# select_load.net
KiCad netlist of a schematic drawn in Altium Designer
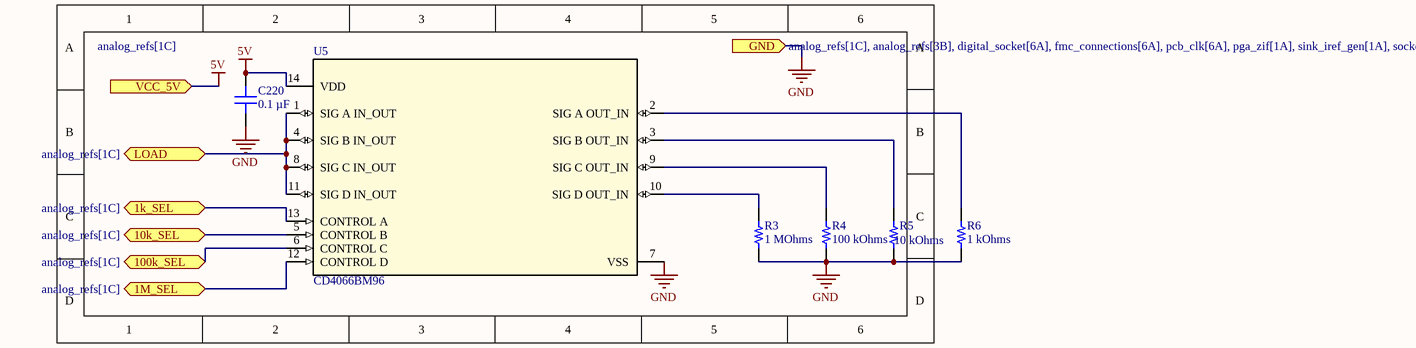
[diagram p0: select_load.SchDoc]

(export (version "E")
  (design (tool "Eeschema 10.0.6"))
  (components
    (comp (ref "C220")
      (value "0.1 µF")
      (footprint "CAP 0805_2012")
      (description "CAP CER 0.1UF 16V X7R 0805")
      (fields
        (field (name "PART NUMBER") "160R15W104KV4T")
        (field (name "CAPACITANCE") "0.1 µF")
        (field (name "MANUFACTURER") "Johanson Dielectrics Inc.")
      )
      (libsource (lib "Celestial Altium Library - altium_library") (part "Capacitor"))
    )
    (comp (ref "R3")
      (value "1 MOhms")
      (footprint "YAGEO RES 0805_2012")
      (description "RES 1 MOHM 1% 1/4W 0805")
      (fields (field (name "PART NUMBER") "AC0805FR-7W1ML") (field (name "MANUFACTURER") "Yageo"))
      (libsource (lib "Celestial Altium Library - altium_library") (part "Resistor"))
    )
    (comp (ref "R4")
      (value "100 kOhms")
      (footprint "RES 0805_2012")
      (description "3430 A2 1% 100K 100PPM 1K RL")
      (fields
        (field (name "PART NUMBER") "3430A2F100KTDF")
        (field (name "MANUFACTURER") "TE Connectivity Passive Product")
      )
      (libsource (lib "Celestial Altium Library - altium_library") (part "Resistor"))
    )
    (comp (ref "R5")
      (value "10 kOhms")
      (footprint "RES 0805_2012")
      (description "3430 A2 1% 10K 100PPM 1K RL")
      (fields
        (field (name "PART NUMBER") "3430A2F10KTDF")
        (field (name "MANUFACTURER") "TE Connectivity Passive Product")
      )
      (libsource (lib "Celestial Altium Library - altium_library") (part "Resistor"))
    )
    (comp (ref "R6")
      (value "1 kOhms")
      (footprint "RES 0805_2012")
      (description "RESHIGHPOWERA 0805 1K 1% 1/2W TC")
      (fields (field (name "PART NUMBER") "CHP0805AFX-1001ELF") (field (name "MANUFACTURER") "Bourns Inc."))
      (libsource (lib "Celestial Altium Library - altium_library") (part "Resistor"))
    )
    (comp (ref "U5")
      (value "CD4066BM96")
      (footprint "D0014A_N")
      (description "10-pA on-state leakage current, 20-V, 1:1 (SPST), 4-channel analog switch 14-SOIC -55 to 125")
      (fields (field (name "COPYRIGHT") "Copyright (C) 2026 Ultra Librarian. All rights reserved."))
      (libsource (lib "Logic") (part "CD4066BM96"))
    )
  )
  (nets
    (net (code "1") (name "/1M_SEL") (class "Default")
      (node (ref "U5") (pin "12") (pinfunction "CONTROL_D_12") (pintype "input"))
    )
    (net (code "2") (name "/1k_SEL") (class "Default")
      (node (ref "U5") (pin "13") (pinfunction "CONTROL_A_13") (pintype "input"))
    )
    (net (code "3") (name "/10k_SEL") (class "Default")
      (node (ref "U5") (pin "5") (pinfunction "CONTROL_B_5") (pintype "input"))
    )
    (net (code "4") (name "/100k_SEL") (class "Default")
      (node (ref "U5") (pin "6") (pinfunction "CONTROL_C_6") (pintype "input"))
    )
    (net (code "5") (name "/LOAD") (class "Default")
      (node (ref "U5") (pin "1") (pinfunction "SIG_A_IN_OUT_1") (pintype "bidirectional"))
      (node (ref "U5") (pin "11") (pinfunction "SIG_D_IN_OUT_11") (pintype "bidirectional"))
      (node (ref "U5") (pin "4") (pinfunction "SIG_B_IN_OUT_4") (pintype "bidirectional"))
      (node (ref "U5") (pin "8") (pinfunction "SIG_C_IN_OUT_8") (pintype "bidirectional"))
    )
    (net (code "6") (name "5V") (class "Default")
      (node (ref "C220") (pin "2") (pinfunction "2_2") (pintype "passive"))
      (node (ref "U5") (pin "14") (pinfunction "VDD_14") (pintype "power_in"))
    )
    (net (code "7") (name "GND") (class "Default")
      (node (ref "C220") (pin "1") (pinfunction "1_1") (pintype "passive"))
      (node (ref "R3") (pin "1") (pinfunction "1_1") (pintype "passive"))
      (node (ref "R4") (pin "1") (pinfunction "1_1") (pintype "passive"))
      (node (ref "R5") (pin "1") (pinfunction "1_1") (pintype "passive"))
      (node (ref "R6") (pin "1") (pinfunction "1_1") (pintype "passive"))
      (node (ref "U5") (pin "7") (pinfunction "VSS_7") (pintype "power_in"))
    )
    (net (code "8") (name "Net-(U5-SIG_A_OUT_IN)") (class "Default")
      (node (ref "R6") (pin "2") (pinfunction "2_2") (pintype "passive"))
      (node (ref "U5") (pin "2") (pinfunction "SIG_A_OUT_IN_2") (pintype "bidirectional"))
    )
    (net (code "9") (name "Net-(U5-SIG_B_OUT_IN)") (class "Default")
      (node (ref "R5") (pin "2") (pinfunction "2_2") (pintype "passive"))
      (node (ref "U5") (pin "3") (pinfunction "SIG_B_OUT_IN_3") (pintype "bidirectional"))
    )
    (net (code "10") (name "Net-(U5-SIG_C_OUT_IN)") (class "Default")
      (node (ref "R4") (pin "2") (pinfunction "2_2") (pintype "passive"))
      (node (ref "U5") (pin "9") (pinfunction "SIG_C_OUT_IN_9") (pintype "bidirectional"))
    )
    (net (code "11") (name "Net-(U5-SIG_D_OUT_IN)") (class "Default")
      (node (ref "R3") (pin "2") (pinfunction "2_2") (pintype "passive"))
      (node (ref "U5") (pin "10") (pinfunction "SIG_D_OUT_IN_10") (pintype "bidirectional"))
    )
  )
)
